# POWER.net
KiCad netlist of a schematic drawn in Altium Designer
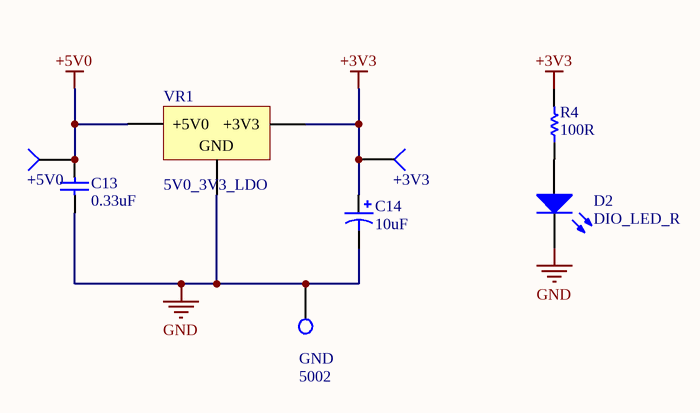
[diagram p0: POWER.SchDoc]

(export (version "E")
  (design (tool "Eeschema 10.0.6"))
  (components
    (comp (ref "C13")
      (value "0.33uF")
      (footprint "CAPC0603(1608)55_N")
      (description "CAP CER 0.33UF 16V X7R 0603")
      (fields
        (field (name "MPN") "GCM188R71C334KA37D")
        (field (name "MANUFACTURER") "Murata Electronics North America")
      )
      (libsource (lib "UWRT_Schematic_Library_2019") (part "CAP_0.33uF_16V_0603"))
    )
    (comp (ref "C14")
      (value "10uF")
      (footprint "AVX-CAPC3528_V")
      (description "Capacitor, Tantalum, 10uF 10% 20V MCCT-B (3528)")
      (fields (field (name "MPN") "CC0603MRX5R6BB106") (field (name "MANUFACTURER") "Yageo"))
      (libsource (lib "UWRT_Schematic_Library_2019") (part "CAP_10uF_0603_POL"))
    )
    (comp (ref "D2")
      (value "DIO_LED_R")
      (footprint "LED_0805_LINE")
      (description "LED RED DIFFUSED 0805 SMD")
      (fields (field (name "MANUFACTURER") "OSRAM") (field (name "MPN") "LS R976-NR-1"))
      (libsource (lib "UWRT_Schematic_Library_2019") (part "DIO_LED_R"))
    )
    (comp (ref "R4")
      (value "100R")
      (footprint "RESC0603(1608)_N")
      (description "RES SMD 100 OHM 1% 1/10W 0603")
      (fields (field (name "MANUFACTURER") "Yageo") (field (name "TOLERANCE") "1%"))
      (libsource (lib "UWRT_Schematic_Library_2019") (part "RES_100R_0603"))
    )
    (comp (ref "TP3")
      (value "+5V0")
      (footprint "TESTPOINT")
      (libsource (lib "UWRT_Schematic_Library_2019") (part "TESTPOINT_SMD"))
    )
    (comp (ref "TP4")
      (value "+3V3")
      (footprint "TESTPOINT")
      (libsource (lib "UWRT_Schematic_Library_2019") (part "TESTPOINT_SMD"))
    )
    (comp (ref "TP5")
      (value "GND")
      (footprint "TESTPOINT_LOOP")
      (description "PC TEST POINT MINIATURE WHITE")
      (fields
        (field (name "DIGIKEY PART NUMBER") "36-5002-ND")
        (field (name "MANUFACTURER") "Keystone Electronics")
        (field (name "MPN") "5002")
      )
      (libsource (lib "UWRT_Schematic_Library_2019") (part "TESTPOINT_LOOP"))
    )
    (comp (ref "VR1")
      (value "5V0_3V3_LDO")
      (footprint "UWRT_Footprint_Library_2019:VOLTAGE_REGULATOR")
      (description "IC REG LINEAR 3.3V 1A DPAK")
      (fields (field (name "MANUFACTURER") "ON Semiconductor") (field (name "MPN") "NCP1117DT33T5G"))
      (libsource (lib "UWRT_Schematic_Library_2019") (part "5V0_3V3_LDO"))
    )
  )
  (nets
    (net (code "1") (name "+3V3") (class "Default")
      (node (ref "C14") (pin "1") (pinfunction "1_1") (pintype "passive"))
      (node (ref "R4") (pin "2") (pinfunction "2_2") (pintype "passive"))
      (node (ref "TP4") (pin "1") (pinfunction "=value_1") (pintype "passive"))
      (node (ref "VR1") (pin "2") (pinfunction "+3V3_2") (pintype "passive"))
    )
    (net (code "2") (name "+5V0") (class "Default")
      (node (ref "C13") (pin "2") (pinfunction "2_2") (pintype "passive"))
      (node (ref "TP3") (pin "1") (pinfunction "=value_1") (pintype "passive"))
      (node (ref "VR1") (pin "3") (pinfunction "+5V0_3") (pintype "passive"))
    )
    (net (code "3") (name "GND") (class "Default")
      (node (ref "C13") (pin "1") (pinfunction "1_1") (pintype "passive"))
      (node (ref "C14") (pin "2") (pinfunction "2_2") (pintype "passive"))
      (node (ref "D2") (pin "2") (pinfunction "K_2") (pintype "passive"))
      (node (ref "TP5") (pin "1") (pinfunction "=value_1") (pintype "passive"))
      (node (ref "VR1") (pin "1") (pinfunction "GND_1") (pintype "passive"))
    )
    (net (code "4") (name "Net-(D2-A)") (class "Default")
      (node (ref "D2") (pin "1") (pinfunction "A_1") (pintype "passive"))
      (node (ref "R4") (pin "1") (pinfunction "1_1") (pintype "passive"))
    )
  )
)
